# V3__RS485.net
KiCad netlist of a schematic drawn in Altium Designer
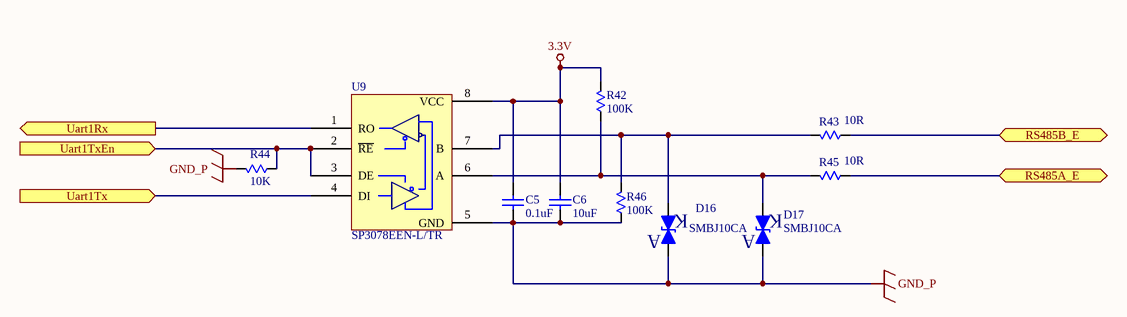
[diagram p0: 海关全向本体电路板V3_扩展RS485通信.SchDoc]

(export (version "E")
  (design (tool "Eeschema 10.0.6"))
  (components
    (comp (ref "C5")
      (value "0.1uF")
      (footprint "C0603-S")
      (description "CAP")
      (fields (field (name "PUBLISHER") "Altium Limited"))
      (libsource (lib "Passive Components Class") (part "CAP"))
    )
    (comp (ref "C6")
      (value "10uF")
      (footprint "C0603-S")
      (description "CAP")
      (fields (field (name "PUBLISHER") "Altium Limited"))
      (libsource (lib "Passive Components Class") (part "CAP"))
    )
    (comp (ref "D16")
      (value "SMBJ10CA")
      (footprint "UPTECH-贴片元件:SMB-S")
      (libsource (lib "MhSchlib") (part "BS0300N"))
    )
    (comp (ref "D17")
      (value "SMBJ10CA")
      (footprint "UPTECH-贴片元件:SMB-S")
      (libsource (lib "MhSchlib") (part "BS0300N"))
    )
    (comp (ref "R42")
      (value "100K")
      (footprint "R0603-S")
      (description "Resistor")
      (fields (field (name "PUBLISHER") "Altium Limited"))
      (libsource (lib "") (part "RES_1"))
    )
    (comp (ref "R43")
      (value "10R")
      (footprint "R1206-S")
      (description "Resistor")
      (fields (field (name "PUBLISHER") "Altium Limited"))
      (libsource (lib "Passive Components Class") (part "RES"))
    )
    (comp (ref "R44")
      (value "10K")
      (footprint "R0603-S")
      (description "Resistor")
      (fields (field (name "PUBLISHER") "Altium Limited"))
      (libsource (lib "Passive Components Class") (part "RES"))
    )
    (comp (ref "R45")
      (value "10R")
      (footprint "R1206-S")
      (description "Resistor")
      (fields (field (name "PUBLISHER") "Altium Limited"))
      (libsource (lib "Passive Components Class") (part "RES"))
    )
    (comp (ref "R46")
      (value "100K")
      (footprint "R0603-S")
      (description "Resistor")
      (fields (field (name "PUBLISHER") "Altium Limited"))
      (libsource (lib "") (part "RES_1"))
    )
    (comp (ref "U9")
      (value "SP3078EEN-L/TR")
      (footprint "SO8-150")
      (libsource (lib "Interface Class") (part "SP3078EEN"))
    )
  )
  (nets
    (net (code "1") (name "/RS485A_E") (class "Default")
      (node (ref "R45") (pin "1") (pinfunction "1_1") (pintype "passive"))
    )
    (net (code "2") (name "/RS485B_E") (class "Default")
      (node (ref "R43") (pin "1") (pinfunction "1_1") (pintype "passive"))
    )
    (net (code "3") (name "/Uart1Rx") (class "Default")
      (node (ref "U9") (pin "1") (pinfunction "RO_1") (pintype "passive"))
    )
    (net (code "4") (name "/Uart1Tx") (class "Default")
      (node (ref "U9") (pin "4") (pinfunction "DI_4") (pintype "passive"))
    )
    (net (code "5") (name "/Uart1TxEn") (class "Default")
      (node (ref "R44") (pin "1") (pinfunction "1_1") (pintype "passive"))
      (node (ref "U9") (pin "2") (pinfunction "~{RE}_2") (pintype "passive"))
      (node (ref "U9") (pin "3") (pinfunction "DE_3") (pintype "passive"))
    )
    (net (code "6") (name "3.3V") (class "Default")
      (node (ref "C5") (pin "2") (pinfunction "2_2") (pintype "passive"))
      (node (ref "C6") (pin "2") (pinfunction "2_2") (pintype "passive"))
      (node (ref "R42") (pin "2") (pinfunction "2_2") (pintype "passive"))
      (node (ref "U9") (pin "8") (pinfunction "VCC_8") (pintype "passive"))
    )
    (net (code "7") (name "GND_P") (class "Default")
      (node (ref "C5") (pin "1") (pinfunction "1_1") (pintype "passive"))
      (node (ref "C6") (pin "1") (pinfunction "1_1") (pintype "passive"))
      (node (ref "D16") (pin "1") (pinfunction "A_1") (pintype "passive"))
      (node (ref "D17") (pin "1") (pinfunction "A_1") (pintype "passive"))
      (node (ref "R44") (pin "2") (pinfunction "2_2") (pintype "passive"))
      (node (ref "R46") (pin "1") (pinfunction "1_1") (pintype "passive"))
      (node (ref "U9") (pin "5") (pinfunction "GND_5") (pintype "passive"))
    )
    (net (code "8") (name "Net-(D16-K)") (class "Default")
      (node (ref "D16") (pin "2") (pinfunction "K_2") (pintype "passive"))
      (node (ref "R43") (pin "2") (pinfunction "2_2") (pintype "passive"))
      (node (ref "R46") (pin "2") (pinfunction "2_2") (pintype "passive"))
      (node (ref "U9") (pin "7") (pinfunction "B_7") (pintype "passive"))
    )
    (net (code "9") (name "Net-(D17-K)") (class "Default")
      (node (ref "D17") (pin "2") (pinfunction "K_2") (pintype "passive"))
      (node (ref "R42") (pin "1") (pinfunction "1_1") (pintype "passive"))
      (node (ref "R45") (pin "2") (pinfunction "2_2") (pintype "passive"))
      (node (ref "U9") (pin "6") (pinfunction "A_6") (pintype "passive"))
    )
  )
)
